# MOS.net
KiCad netlist of a schematic drawn in Altium Designer
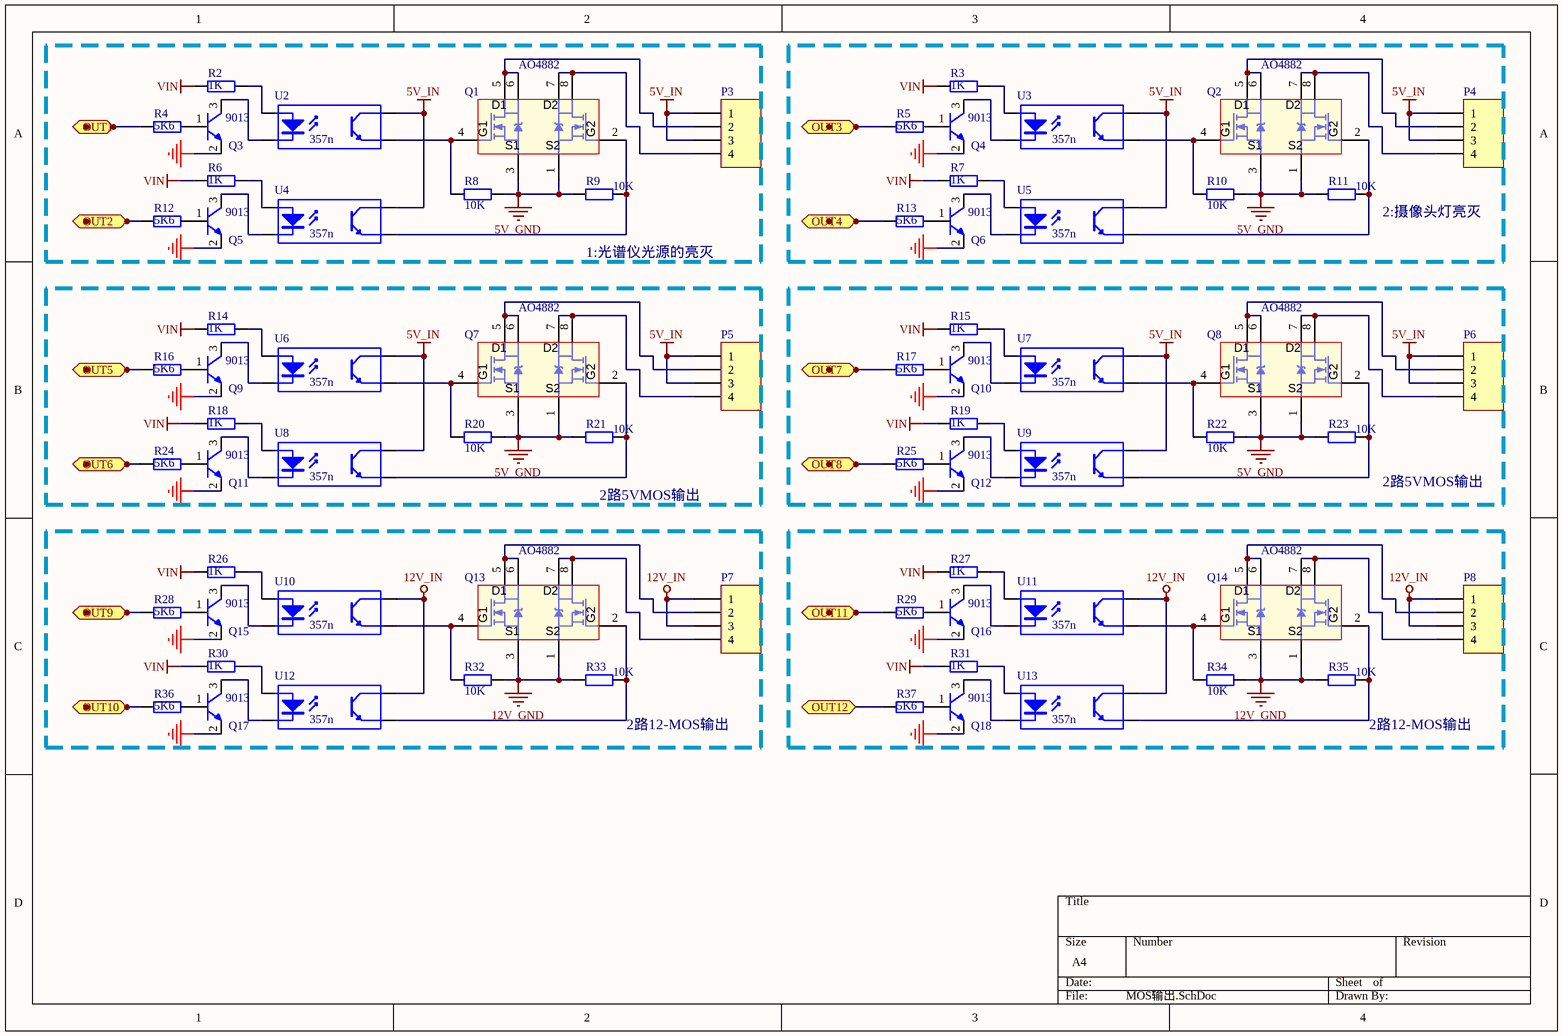
[diagram p0: MOS输出.SchDoc]

(export (version "E")
  (design (tool "Eeschema 10.0.6"))
  (components
    (comp (ref "P3")
      (value "~")
      (footprint "CAN3.81W/4")
      (description "Header, 4-Pin")
      (fields (field (name "PUBLISHER") "Altium Limited"))
      (libsource (lib "Miscellaneous Connectors") (part "Header 4"))
    )
    (comp (ref "P4")
      (value "~")
      (footprint "CAN3.81W/4")
      (description "Header, 4-Pin")
      (fields (field (name "PUBLISHER") "Altium Limited"))
      (libsource (lib "Miscellaneous Connectors") (part "Header 4"))
    )
    (comp (ref "P5")
      (value "~")
      (footprint "CAN3.81W/4")
      (description "Header, 4-Pin")
      (fields (field (name "PUBLISHER") "Altium Limited"))
      (libsource (lib "Miscellaneous Connectors") (part "Header 4"))
    )
    (comp (ref "P6")
      (value "~")
      (footprint "CAN3.81W/4")
      (description "Header, 4-Pin")
      (fields (field (name "PUBLISHER") "Altium Limited"))
      (libsource (lib "Miscellaneous Connectors") (part "Header 4"))
    )
    (comp (ref "P7")
      (value "~")
      (footprint "CAN3.81W/4")
      (description "Header, 4-Pin")
      (fields (field (name "PUBLISHER") "Altium Limited"))
      (libsource (lib "Miscellaneous Connectors") (part "Header 4"))
    )
    (comp (ref "P8")
      (value "~")
      (footprint "CAN3.81W/4")
      (description "Header, 4-Pin")
      (fields (field (name "PUBLISHER") "Altium Limited"))
      (libsource (lib "Miscellaneous Connectors") (part "Header 4"))
    )
    (comp (ref "Q1")
      (value "AO4882")
      (footprint "so8")
      (description "Mosfet Array 2 N-Channel (Dual) 40V 8A 2W Surface Mount 8-SOIC")
      (fields (field (name "MF") "Alpha & Omega Semiconductor Inc."))
      (libsource (lib "TMC5160_RevA") (part "AO4882 MOSFET 2N-CH 40V 8A 8SOIC"))
    )
    (comp (ref "Q2")
      (value "AO4882")
      (footprint "so8")
      (description "Mosfet Array 2 N-Channel (Dual) 40V 8A 2W Surface Mount 8-SOIC")
      (fields (field (name "MF") "Alpha & Omega Semiconductor Inc."))
      (libsource (lib "TMC5160_RevA") (part "AO4882 MOSFET 2N-CH 40V 8A 8SOIC"))
    )
    (comp (ref "Q3") (value "9013") (footprint "sot-23") (libsource (lib "*") (part "NPNBT")))
    (comp (ref "Q4") (value "9013") (footprint "sot-23") (libsource (lib "*") (part "NPNBT")))
    (comp (ref "Q5") (value "9013") (footprint "sot-23") (libsource (lib "*") (part "NPNBT")))
    (comp (ref "Q6") (value "9013") (footprint "sot-23") (libsource (lib "*") (part "NPNBT")))
    (comp (ref "Q7")
      (value "AO4882")
      (footprint "so8")
      (description "Mosfet Array 2 N-Channel (Dual) 40V 8A 2W Surface Mount 8-SOIC")
      (fields (field (name "MF") "Alpha & Omega Semiconductor Inc."))
      (libsource (lib "TMC5160_RevA") (part "AO4882 MOSFET 2N-CH 40V 8A 8SOIC"))
    )
    (comp (ref "Q8")
      (value "AO4882")
      (footprint "so8")
      (description "Mosfet Array 2 N-Channel (Dual) 40V 8A 2W Surface Mount 8-SOIC")
      (fields (field (name "MF") "Alpha & Omega Semiconductor Inc."))
      (libsource (lib "TMC5160_RevA") (part "AO4882 MOSFET 2N-CH 40V 8A 8SOIC"))
    )
    (comp (ref "Q9") (value "9013") (footprint "sot-23") (libsource (lib "*") (part "NPNBT")))
    (comp (ref "Q10") (value "9013") (footprint "sot-23") (libsource (lib "*") (part "NPNBT")))
    (comp (ref "Q11") (value "9013") (footprint "sot-23") (libsource (lib "*") (part "NPNBT")))
    (comp (ref "Q12") (value "9013") (footprint "sot-23") (libsource (lib "*") (part "NPNBT")))
    (comp (ref "Q13")
      (value "AO4882")
      (footprint "so8")
      (description "Mosfet Array 2 N-Channel (Dual) 40V 8A 2W Surface Mount 8-SOIC")
      (fields (field (name "MF") "Alpha & Omega Semiconductor Inc."))
      (libsource (lib "TMC5160_RevA") (part "AO4882 MOSFET 2N-CH 40V 8A 8SOIC"))
    )
    (comp (ref "Q14")
      (value "AO4882")
      (footprint "so8")
      (description "Mosfet Array 2 N-Channel (Dual) 40V 8A 2W Surface Mount 8-SOIC")
      (fields (field (name "MF") "Alpha & Omega Semiconductor Inc."))
      (libsource (lib "TMC5160_RevA") (part "AO4882 MOSFET 2N-CH 40V 8A 8SOIC"))
    )
    (comp (ref "Q15") (value "9013") (footprint "sot-23") (libsource (lib "*") (part "NPNBT")))
    (comp (ref "Q16") (value "9013") (footprint "sot-23") (libsource (lib "*") (part "NPNBT")))
    (comp (ref "Q17") (value "9013") (footprint "sot-23") (libsource (lib "*") (part "NPNBT")))
    (comp (ref "Q18") (value "9013") (footprint "sot-23") (libsource (lib "*") (part "NPNBT")))
    (comp (ref "R2")
      (value "1K")
      (footprint "1608")
      (description "Resistor")
      (fields (field (name "PUBLISHER") "Altium Limited"))
      (libsource (lib "*") (part "Res2"))
    )
    (comp (ref "R3")
      (value "1K")
      (footprint "1608")
      (description "Resistor")
      (fields (field (name "PUBLISHER") "Altium Limited"))
      (libsource (lib "*") (part "Res2"))
    )
    (comp (ref "R4")
      (value "5K6")
      (footprint "1608")
      (description "Resistor")
      (fields (field (name "PUBLISHER") "Altium Limited"))
      (libsource (lib "*") (part "Res2"))
    )
    (comp (ref "R5")
      (value "5K6")
      (footprint "1608")
      (description "Resistor")
      (fields (field (name "PUBLISHER") "Altium Limited"))
      (libsource (lib "*") (part "Res2"))
    )
    (comp (ref "R6")
      (value "1K")
      (footprint "1608")
      (description "Resistor")
      (fields (field (name "PUBLISHER") "Altium Limited"))
      (libsource (lib "*") (part "Res2"))
    )
    (comp (ref "R7")
      (value "1K")
      (footprint "1608")
      (description "Resistor")
      (fields (field (name "PUBLISHER") "Altium Limited"))
      (libsource (lib "*") (part "Res2"))
    )
    (comp (ref "R8")
      (value "10K")
      (footprint "1608")
      (description "Resistor")
      (fields (field (name "PUBLISHER") "Altium Limited"))
      (libsource (lib "*") (part "Res2"))
    )
    (comp (ref "R9")
      (value "10K")
      (footprint "1608")
      (description "Resistor")
      (fields (field (name "PUBLISHER") "Altium Limited"))
      (libsource (lib "*") (part "Res2"))
    )
    (comp (ref "R10")
      (value "10K")
      (footprint "1608")
      (description "Resistor")
      (fields (field (name "PUBLISHER") "Altium Limited"))
      (libsource (lib "*") (part "Res2"))
    )
    (comp (ref "R11")
      (value "10K")
      (footprint "1608")
      (description "Resistor")
      (fields (field (name "PUBLISHER") "Altium Limited"))
      (libsource (lib "*") (part "Res2"))
    )
    (comp (ref "R12")
      (value "5K6")
      (footprint "1608")
      (description "Resistor")
      (fields (field (name "PUBLISHER") "Altium Limited"))
      (libsource (lib "*") (part "Res2"))
    )
    (comp (ref "R13")
      (value "5K6")
      (footprint "1608")
      (description "Resistor")
      (fields (field (name "PUBLISHER") "Altium Limited"))
      (libsource (lib "*") (part "Res2"))
    )
    (comp (ref "R14")
      (value "1K")
      (footprint "1608")
      (description "Resistor")
      (fields (field (name "PUBLISHER") "Altium Limited"))
      (libsource (lib "*") (part "Res2"))
    )
    (comp (ref "R15")
      (value "1K")
      (footprint "1608")
      (description "Resistor")
      (fields (field (name "PUBLISHER") "Altium Limited"))
      (libsource (lib "*") (part "Res2"))
    )
    (comp (ref "R16")
      (value "5K6")
      (footprint "1608")
      (description "Resistor")
      (fields (field (name "PUBLISHER") "Altium Limited"))
      (libsource (lib "*") (part "Res2"))
    )
    (comp (ref "R17")
      (value "5K6")
      (footprint "1608")
      (description "Resistor")
      (fields (field (name "PUBLISHER") "Altium Limited"))
      (libsource (lib "*") (part "Res2"))
    )
    (comp (ref "R18")
      (value "1K")
      (footprint "1608")
      (description "Resistor")
      (fields (field (name "PUBLISHER") "Altium Limited"))
      (libsource (lib "*") (part "Res2"))
    )
    (comp (ref "R19")
      (value "1K")
      (footprint "1608")
      (description "Resistor")
      (fields (field (name "PUBLISHER") "Altium Limited"))
      (libsource (lib "*") (part "Res2"))
    )
    (comp (ref "R20")
      (value "10K")
      (footprint "1608")
      (description "Resistor")
      (fields (field (name "PUBLISHER") "Altium Limited"))
      (libsource (lib "*") (part "Res2"))
    )
    (comp (ref "R21")
      (value "10K")
      (footprint "1608")
      (description "Resistor")
      (fields (field (name "PUBLISHER") "Altium Limited"))
      (libsource (lib "*") (part "Res2"))
    )
    (comp (ref "R22")
      (value "10K")
      (footprint "1608")
      (description "Resistor")
      (fields (field (name "PUBLISHER") "Altium Limited"))
      (libsource (lib "*") (part "Res2"))
    )
    (comp (ref "R23")
      (value "10K")
      (footprint "1608")
      (description "Resistor")
      (fields (field (name "PUBLISHER") "Altium Limited"))
      (libsource (lib "*") (part "Res2"))
    )
    (comp (ref "R24")
      (value "5K6")
      (footprint "1608")
      (description "Resistor")
      (fields (field (name "PUBLISHER") "Altium Limited"))
      (libsource (lib "*") (part "Res2"))
    )
    (comp (ref "R25")
      (value "5K6")
      (footprint "1608")
      (description "Resistor")
      (fields (field (name "PUBLISHER") "Altium Limited"))
      (libsource (lib "*") (part "Res2"))
    )
    (comp (ref "R26")
      (value "1K")
      (footprint "1608")
      (description "Resistor")
      (fields (field (name "PUBLISHER") "Altium Limited"))
      (libsource (lib "*") (part "Res2"))
    )
    (comp (ref "R27")
      (value "1K")
      (footprint "1608")
      (description "Resistor")
      (fields (field (name "PUBLISHER") "Altium Limited"))
      (libsource (lib "*") (part "Res2"))
    )
    (comp (ref "R28")
      (value "5K6")
      (footprint "1608")
      (description "Resistor")
      (fields (field (name "PUBLISHER") "Altium Limited"))
      (libsource (lib "*") (part "Res2"))
    )
    (comp (ref "R29")
      (value "5K6")
      (footprint "1608")
      (description "Resistor")
      (fields (field (name "PUBLISHER") "Altium Limited"))
      (libsource (lib "*") (part "Res2"))
    )
    (comp (ref "R30")
      (value "1K")
      (footprint "1608")
      (description "Resistor")
      (fields (field (name "PUBLISHER") "Altium Limited"))
      (libsource (lib "*") (part "Res2"))
    )
    (comp (ref "R31")
      (value "1K")
      (footprint "1608")
      (description "Resistor")
      (fields (field (name "PUBLISHER") "Altium Limited"))
      (libsource (lib "*") (part "Res2"))
    )
    (comp (ref "R32")
      (value "10K")
      (footprint "1608")
      (description "Resistor")
      (fields (field (name "PUBLISHER") "Altium Limited"))
      (libsource (lib "*") (part "Res2"))
    )
    (comp (ref "R33")
      (value "10K")
      (footprint "1608")
      (description "Resistor")
      (fields (field (name "PUBLISHER") "Altium Limited"))
      (libsource (lib "*") (part "Res2"))
    )
    (comp (ref "R34")
      (value "10K")
      (footprint "1608")
      (description "Resistor")
      (fields (field (name "PUBLISHER") "Altium Limited"))
      (libsource (lib "*") (part "Res2"))
    )
    (comp (ref "R35")
      (value "10K")
      (footprint "1608")
      (description "Resistor")
      (fields (field (name "PUBLISHER") "Altium Limited"))
      (libsource (lib "*") (part "Res2"))
    )
    (comp (ref "R36")
      (value "5K6")
      (footprint "1608")
      (description "Resistor")
      (fields (field (name "PUBLISHER") "Altium Limited"))
      (libsource (lib "*") (part "Res2"))
    )
    (comp (ref "R37")
      (value "5K6")
      (footprint "1608")
      (description "Resistor")
      (fields (field (name "PUBLISHER") "Altium Limited"))
      (libsource (lib "*") (part "Res2"))
    )
    (comp (ref "U2")
      (value "357n")
      (footprint "375N")
      (description "4-Pin Phototransistor Optocoupler")
      (fields (field (name "PUBLISHER") "Altium Limited"))
      (libsource (lib "Miscellaneous Devices") (part "Optoisolator1"))
    )
    (comp (ref "U3")
      (value "357n")
      (footprint "375N")
      (description "4-Pin Phototransistor Optocoupler")
      (fields (field (name "PUBLISHER") "Altium Limited"))
      (libsource (lib "Miscellaneous Devices") (part "Optoisolator1"))
    )
    (comp (ref "U4")
      (value "357n")
      (footprint "375N")
      (description "4-Pin Phototransistor Optocoupler")
      (fields (field (name "PUBLISHER") "Altium Limited"))
      (libsource (lib "Miscellaneous Devices") (part "Optoisolator1"))
    )
    (comp (ref "U5")
      (value "357n")
      (footprint "375N")
      (description "4-Pin Phototransistor Optocoupler")
      (fields (field (name "PUBLISHER") "Altium Limited"))
      (libsource (lib "Miscellaneous Devices") (part "Optoisolator1"))
    )
    (comp (ref "U6")
      (value "357n")
      (footprint "375N")
      (description "4-Pin Phototransistor Optocoupler")
      (fields (field (name "PUBLISHER") "Altium Limited"))
      (libsource (lib "Miscellaneous Devices") (part "Optoisolator1"))
    )
    (comp (ref "U7")
      (value "357n")
      (footprint "375N")
      (description "4-Pin Phototransistor Optocoupler")
      (fields (field (name "PUBLISHER") "Altium Limited"))
      (libsource (lib "Miscellaneous Devices") (part "Optoisolator1"))
    )
    (comp (ref "U8")
      (value "357n")
      (footprint "375N")
      (description "4-Pin Phototransistor Optocoupler")
      (fields (field (name "PUBLISHER") "Altium Limited"))
      (libsource (lib "Miscellaneous Devices") (part "Optoisolator1"))
    )
    (comp (ref "U9")
      (value "357n")
      (footprint "375N")
      (description "4-Pin Phototransistor Optocoupler")
      (fields (field (name "PUBLISHER") "Altium Limited"))
      (libsource (lib "Miscellaneous Devices") (part "Optoisolator1"))
    )
    (comp (ref "U10")
      (value "357n")
      (footprint "375N")
      (description "4-Pin Phototransistor Optocoupler")
      (fields (field (name "PUBLISHER") "Altium Limited"))
      (libsource (lib "Miscellaneous Devices") (part "Optoisolator1"))
    )
    (comp (ref "U11")
      (value "357n")
      (footprint "375N")
      (description "4-Pin Phototransistor Optocoupler")
      (fields (field (name "PUBLISHER") "Altium Limited"))
      (libsource (lib "Miscellaneous Devices") (part "Optoisolator1"))
    )
    (comp (ref "U12")
      (value "357n")
      (footprint "375N")
      (description "4-Pin Phototransistor Optocoupler")
      (fields (field (name "PUBLISHER") "Altium Limited"))
      (libsource (lib "Miscellaneous Devices") (part "Optoisolator1"))
    )
    (comp (ref "U13")
      (value "357n")
      (footprint "375N")
      (description "4-Pin Phototransistor Optocoupler")
      (fields (field (name "PUBLISHER") "Altium Limited"))
      (libsource (lib "Miscellaneous Devices") (part "Optoisolator1"))
    )
  )
  (nets
    (net (code "1") (name "/OUT1") (class "Default")
      (node (ref "R4") (pin "2") (pinfunction "2_2") (pintype "passive"))
    )
    (net (code "2") (name "/OUT2") (class "Default")
      (node (ref "R12") (pin "2") (pinfunction "2_2") (pintype "passive"))
    )
    (net (code "3") (name "/OUT3") (class "Default")
      (node (ref "R5") (pin "2") (pinfunction "2_2") (pintype "passive"))
    )
    (net (code "4") (name "/OUT4") (class "Default")
      (node (ref "R13") (pin "2") (pinfunction "2_2") (pintype "passive"))
    )
    (net (code "5") (name "/OUT5") (class "Default")
      (node (ref "R16") (pin "2") (pinfunction "2_2") (pintype "passive"))
    )
    (net (code "6") (name "/OUT6") (class "Default")
      (node (ref "R24") (pin "2") (pinfunction "2_2") (pintype "passive"))
    )
    (net (code "7") (name "/OUT7") (class "Default")
      (node (ref "R17") (pin "2") (pinfunction "2_2") (pintype "passive"))
    )
    (net (code "8") (name "/OUT8") (class "Default")
      (node (ref "R25") (pin "2") (pinfunction "2_2") (pintype "passive"))
    )
    (net (code "9") (name "/OUT9") (class "Default")
      (node (ref "R28") (pin "2") (pinfunction "2_2") (pintype "passive"))
    )
    (net (code "10") (name "/OUT10") (class "Default")
      (node (ref "R36") (pin "2") (pinfunction "2_2") (pintype "passive"))
    )
    (net (code "11") (name "/OUT11") (class "Default")
      (node (ref "R29") (pin "2") (pinfunction "2_2") (pintype "passive"))
    )
    (net (code "12") (name "/OUT12") (class "Default")
      (node (ref "R37") (pin "2") (pinfunction "2_2") (pintype "passive"))
    )
    (net (code "13") (name "5V_GND") (class "Default")
      (node (ref "Q1") (pin "1") (pinfunction "S2_1") (pintype "passive"))
      (node (ref "Q1") (pin "3") (pinfunction "S1_3") (pintype "passive"))
      (node (ref "Q2") (pin "1") (pinfunction "S2_1") (pintype "passive"))
      (node (ref "Q2") (pin "3") (pinfunction "S1_3") (pintype "passive"))
      (node (ref "Q7") (pin "1") (pinfunction "S2_1") (pintype "passive"))
      (node (ref "Q7") (pin "3") (pinfunction "S1_3") (pintype "passive"))
      (node (ref "Q8") (pin "1") (pinfunction "S2_1") (pintype "passive"))
      (node (ref "Q8") (pin "3") (pinfunction "S1_3") (pintype "passive"))
      (node (ref "R10") (pin "1") (pinfunction "1_1") (pintype "passive"))
      (node (ref "R11") (pin "2") (pinfunction "2_2") (pintype "passive"))
      (node (ref "R20") (pin "1") (pinfunction "1_1") (pintype "passive"))
      (node (ref "R21") (pin "2") (pinfunction "2_2") (pintype "passive"))
      (node (ref "R22") (pin "1") (pinfunction "1_1") (pintype "passive"))
      (node (ref "R23") (pin "2") (pinfunction "2_2") (pintype "passive"))
      (node (ref "R8") (pin "1") (pinfunction "1_1") (pintype "passive"))
      (node (ref "R9") (pin "2") (pinfunction "2_2") (pintype "passive"))
    )
    (net (code "14") (name "5V_IN") (class "Default")
      (node (ref "P3") (pin "1") (pinfunction "1_1") (pintype "passive"))
      (node (ref "P3") (pin "3") (pinfunction "3_3") (pintype "passive"))
      (node (ref "P4") (pin "1") (pinfunction "1_1") (pintype "passive"))
      (node (ref "P4") (pin "3") (pinfunction "3_3") (pintype "passive"))
      (node (ref "P5") (pin "1") (pinfunction "1_1") (pintype "passive"))
      (node (ref "P5") (pin "3") (pinfunction "3_3") (pintype "passive"))
      (node (ref "P6") (pin "1") (pinfunction "1_1") (pintype "passive"))
      (node (ref "P6") (pin "3") (pinfunction "3_3") (pintype "passive"))
      (node (ref "U2") (pin "4") (pinfunction "C_4") (pintype "passive"))
      (node (ref "U3") (pin "4") (pinfunction "C_4") (pintype "passive"))
      (node (ref "U4") (pin "4") (pinfunction "C_4") (pintype "passive"))
      (node (ref "U5") (pin "4") (pinfunction "C_4") (pintype "passive"))
      (node (ref "U6") (pin "4") (pinfunction "C_4") (pintype "passive"))
      (node (ref "U7") (pin "4") (pinfunction "C_4") (pintype "passive"))
      (node (ref "U8") (pin "4") (pinfunction "C_4") (pintype "passive"))
      (node (ref "U9") (pin "4") (pinfunction "C_4") (pintype "passive"))
    )
    (net (code "15") (name "12V_GND") (class "Default")
      (node (ref "Q13") (pin "1") (pinfunction "S2_1") (pintype "passive"))
      (node (ref "Q13") (pin "3") (pinfunction "S1_3") (pintype "passive"))
      (node (ref "Q14") (pin "1") (pinfunction "S2_1") (pintype "passive"))
      (node (ref "Q14") (pin "3") (pinfunction "S1_3") (pintype "passive"))
      (node (ref "R32") (pin "1") (pinfunction "1_1") (pintype "passive"))
      (node (ref "R33") (pin "2") (pinfunction "2_2") (pintype "passive"))
      (node (ref "R34") (pin "1") (pinfunction "1_1") (pintype "passive"))
      (node (ref "R35") (pin "2") (pinfunction "2_2") (pintype "passive"))
    )
    (net (code "16") (name "12V_IN") (class "Default")
      (node (ref "P7") (pin "1") (pinfunction "1_1") (pintype "passive"))
      (node (ref "P7") (pin "3") (pinfunction "3_3") (pintype "passive"))
      (node (ref "P8") (pin "1") (pinfunction "1_1") (pintype "passive"))
      (node (ref "P8") (pin "3") (pinfunction "3_3") (pintype "passive"))
      (node (ref "U10") (pin "4") (pinfunction "C_4") (pintype "passive"))
      (node (ref "U11") (pin "4") (pinfunction "C_4") (pintype "passive"))
      (node (ref "U12") (pin "4") (pinfunction "C_4") (pintype "passive"))
      (node (ref "U13") (pin "4") (pinfunction "C_4") (pintype "passive"))
    )
    (net (code "17") (name "GND") (class "Default")
      (node (ref "Q10") (pin "2") (pinfunction "E_2") (pintype "passive"))
      (node (ref "Q11") (pin "2") (pinfunction "E_2") (pintype "passive"))
      (node (ref "Q12") (pin "2") (pinfunction "E_2") (pintype "passive"))
      (node (ref "Q15") (pin "2") (pinfunction "E_2") (pintype "passive"))
      (node (ref "Q16") (pin "2") (pinfunction "E_2") (pintype "passive"))
      (node (ref "Q17") (pin "2") (pinfunction "E_2") (pintype "passive"))
      (node (ref "Q18") (pin "2") (pinfunction "E_2") (pintype "passive"))
      (node (ref "Q3") (pin "2") (pinfunction "E_2") (pintype "passive"))
      (node (ref "Q4") (pin "2") (pinfunction "E_2") (pintype "passive"))
      (node (ref "Q5") (pin "2") (pinfunction "E_2") (pintype "passive"))
      (node (ref "Q6") (pin "2") (pinfunction "E_2") (pintype "passive"))
      (node (ref "Q9") (pin "2") (pinfunction "E_2") (pintype "passive"))
    )
    (net (code "18") (name "Net-(P3-Pad2)") (class "Default")
      (node (ref "P3") (pin "2") (pinfunction "2_2") (pintype "passive"))
      (node (ref "Q1") (pin "5") (pinfunction "D1_5") (pintype "passive"))
      (node (ref "Q1") (pin "6") (pinfunction "D1_6") (pintype "passive"))
    )
    (net (code "19") (name "Net-(P3-Pad4)") (class "Default")
      (node (ref "P3") (pin "4") (pinfunction "4_4") (pintype "passive"))
      (node (ref "Q1") (pin "7") (pinfunction "D2_7") (pintype "passive"))
      (node (ref "Q1") (pin "8") (pinfunction "D2_8") (pintype "passive"))
    )
    (net (code "20") (name "Net-(P4-Pad2)") (class "Default")
      (node (ref "P4") (pin "2") (pinfunction "2_2") (pintype "passive"))
      (node (ref "Q2") (pin "5") (pinfunction "D1_5") (pintype "passive"))
      (node (ref "Q2") (pin "6") (pinfunction "D1_6") (pintype "passive"))
    )
    (net (code "21") (name "Net-(P4-Pad4)") (class "Default")
      (node (ref "P4") (pin "4") (pinfunction "4_4") (pintype "passive"))
      (node (ref "Q2") (pin "7") (pinfunction "D2_7") (pintype "passive"))
      (node (ref "Q2") (pin "8") (pinfunction "D2_8") (pintype "passive"))
    )
    (net (code "22") (name "Net-(P5-Pad2)") (class "Default")
      (node (ref "P5") (pin "2") (pinfunction "2_2") (pintype "passive"))
      (node (ref "Q7") (pin "5") (pinfunction "D1_5") (pintype "passive"))
      (node (ref "Q7") (pin "6") (pinfunction "D1_6") (pintype "passive"))
    )
    (net (code "23") (name "Net-(P5-Pad4)") (class "Default")
      (node (ref "P5") (pin "4") (pinfunction "4_4") (pintype "passive"))
      (node (ref "Q7") (pin "7") (pinfunction "D2_7") (pintype "passive"))
      (node (ref "Q7") (pin "8") (pinfunction "D2_8") (pintype "passive"))
    )
    (net (code "24") (name "Net-(P6-Pad2)") (class "Default")
      (node (ref "P6") (pin "2") (pinfunction "2_2") (pintype "passive"))
      (node (ref "Q8") (pin "5") (pinfunction "D1_5") (pintype "passive"))
      (node (ref "Q8") (pin "6") (pinfunction "D1_6") (pintype "passive"))
    )
    (net (code "25") (name "Net-(P6-Pad4)") (class "Default")
      (node (ref "P6") (pin "4") (pinfunction "4_4") (pintype "passive"))
      (node (ref "Q8") (pin "7") (pinfunction "D2_7") (pintype "passive"))
      (node (ref "Q8") (pin "8") (pinfunction "D2_8") (pintype "passive"))
    )
    (net (code "26") (name "Net-(P7-Pad2)") (class "Default")
      (node (ref "P7") (pin "2") (pinfunction "2_2") (pintype "passive"))
      (node (ref "Q13") (pin "5") (pinfunction "D1_5") (pintype "passive"))
      (node (ref "Q13") (pin "6") (pinfunction "D1_6") (pintype "passive"))
    )
    (net (code "27") (name "Net-(P7-Pad4)") (class "Default")
      (node (ref "P7") (pin "4") (pinfunction "4_4") (pintype "passive"))
      (node (ref "Q13") (pin "7") (pinfunction "D2_7") (pintype "passive"))
      (node (ref "Q13") (pin "8") (pinfunction "D2_8") (pintype "passive"))
    )
    (net (code "28") (name "Net-(P8-Pad2)") (class "Default")
      (node (ref "P8") (pin "2") (pinfunction "2_2") (pintype "passive"))
      (node (ref "Q14") (pin "5") (pinfunction "D1_5") (pintype "passive"))
      (node (ref "Q14") (pin "6") (pinfunction "D1_6") (pintype "passive"))
    )
    (net (code "29") (name "Net-(P8-Pad4)") (class "Default")
      (node (ref "P8") (pin "4") (pinfunction "4_4") (pintype "passive"))
      (node (ref "Q14") (pin "7") (pinfunction "D2_7") (pintype "passive"))
      (node (ref "Q14") (pin "8") (pinfunction "D2_8") (pintype "passive"))
    )
    (net (code "30") (name "Net-(Q1-G1)") (class "Default")
      (node (ref "Q1") (pin "4") (pinfunction "G1_4") (pintype "passive"))
      (node (ref "R8") (pin "2") (pinfunction "2_2") (pintype "passive"))
      (node (ref "U2") (pin "3") (pinfunction "E_3") (pintype "passive"))
    )
    (net (code "31") (name "Net-(Q1-G2)") (class "Default")
      (node (ref "Q1") (pin "2") (pinfunction "G2_2") (pintype "passive"))
      (node (ref "R9") (pin "1") (pinfunction "1_1") (pintype "passive"))
      (node (ref "U4") (pin "3") (pinfunction "E_3") (pintype "passive"))
    )
    (net (code "32") (name "Net-(Q2-G1)") (class "Default")
      (node (ref "Q2") (pin "4") (pinfunction "G1_4") (pintype "passive"))
      (node (ref "R10") (pin "2") (pinfunction "2_2") (pintype "passive"))
      (node (ref "U3") (pin "3") (pinfunction "E_3") (pintype "passive"))
    )
    (net (code "33") (name "Net-(Q2-G2)") (class "Default")
      (node (ref "Q2") (pin "2") (pinfunction "G2_2") (pintype "passive"))
      (node (ref "R11") (pin "1") (pinfunction "1_1") (pintype "passive"))
      (node (ref "U5") (pin "3") (pinfunction "E_3") (pintype "passive"))
    )
    (net (code "34") (name "Net-(Q3-B)") (class "Default")
      (node (ref "Q3") (pin "1") (pinfunction "B_1") (pintype "passive"))
      (node (ref "R4") (pin "1") (pinfunction "1_1") (pintype "passive"))
    )
    (net (code "35") (name "Net-(Q3-C)") (class "Default")
      (node (ref "Q3") (pin "3") (pinfunction "C_3") (pintype "passive"))
      (node (ref "U2") (pin "2") (pinfunction "K_2") (pintype "passive"))
    )
    (net (code "36") (name "Net-(Q4-B)") (class "Default")
      (node (ref "Q4") (pin "1") (pinfunction "B_1") (pintype "passive"))
      (node (ref "R5") (pin "1") (pinfunction "1_1") (pintype "passive"))
    )
    (net (code "37") (name "Net-(Q4-C)") (class "Default")
      (node (ref "Q4") (pin "3") (pinfunction "C_3") (pintype "passive"))
      (node (ref "U3") (pin "2") (pinfunction "K_2") (pintype "passive"))
    )
    (net (code "38") (name "Net-(Q5-B)") (class "Default")
      (node (ref "Q5") (pin "1") (pinfunction "B_1") (pintype "passive"))
      (node (ref "R12") (pin "1") (pinfunction "1_1") (pintype "passive"))
    )
    (net (code "39") (name "Net-(Q5-C)") (class "Default")
      (node (ref "Q5") (pin "3") (pinfunction "C_3") (pintype "passive"))
      (node (ref "U4") (pin "2") (pinfunction "K_2") (pintype "passive"))
    )
    (net (code "40") (name "Net-(Q6-B)") (class "Default")
      (node (ref "Q6") (pin "1") (pinfunction "B_1") (pintype "passive"))
      (node (ref "R13") (pin "1") (pinfunction "1_1") (pintype "passive"))
    )
    (net (code "41") (name "Net-(Q6-C)") (class "Default")
      (node (ref "Q6") (pin "3") (pinfunction "C_3") (pintype "passive"))
      (node (ref "U5") (pin "2") (pinfunction "K_2") (pintype "passive"))
    )
    (net (code "42") (name "Net-(Q7-G1)") (class "Default")
      (node (ref "Q7") (pin "4") (pinfunction "G1_4") (pintype "passive"))
      (node (ref "R20") (pin "2") (pinfunction "2_2") (pintype "passive"))
      (node (ref "U6") (pin "3") (pinfunction "E_3") (pintype "passive"))
    )
    (net (code "43") (name "Net-(Q7-G2)") (class "Default")
      (node (ref "Q7") (pin "2") (pinfunction "G2_2") (pintype "passive"))
      (node (ref "R21") (pin "1") (pinfunction "1_1") (pintype "passive"))
      (node (ref "U8") (pin "3") (pinfunction "E_3") (pintype "passive"))
    )
    (net (code "44") (name "Net-(Q8-G1)") (class "Default")
      (node (ref "Q8") (pin "4") (pinfunction "G1_4") (pintype "passive"))
      (node (ref "R22") (pin "2") (pinfunction "2_2") (pintype "passive"))
      (node (ref "U7") (pin "3") (pinfunction "E_3") (pintype "passive"))
    )
    (net (code "45") (name "Net-(Q8-G2)") (class "Default")
      (node (ref "Q8") (pin "2") (pinfunction "G2_2") (pintype "passive"))
      (node (ref "R23") (pin "1") (pinfunction "1_1") (pintype "passive"))
      (node (ref "U9") (pin "3") (pinfunction "E_3") (pintype "passive"))
    )
    (net (code "46") (name "Net-(Q9-B)") (class "Default")
      (node (ref "Q9") (pin "1") (pinfunction "B_1") (pintype "passive"))
      (node (ref "R16") (pin "1") (pinfunction "1_1") (pintype "passive"))
    )
    (net (code "47") (name "Net-(Q9-C)") (class "Default")
      (node (ref "Q9") (pin "3") (pinfunction "C_3") (pintype "passive"))
      (node (ref "U6") (pin "2") (pinfunction "K_2") (pintype "passive"))
    )
    (net (code "48") (name "Net-(Q10-B)") (class "Default")
      (node (ref "Q10") (pin "1") (pinfunction "B_1") (pintype "passive"))
      (node (ref "R17") (pin "1") (pinfunction "1_1") (pintype "passive"))
    )
    (net (code "49") (name "Net-(Q10-C)") (class "Default")
      (node (ref "Q10") (pin "3") (pinfunction "C_3") (pintype "passive"))
      (node (ref "U7") (pin "2") (pinfunction "K_2") (pintype "passive"))
    )
    (net (code "50") (name "Net-(Q11-B)") (class "Default")
      (node (ref "Q11") (pin "1") (pinfunction "B_1") (pintype "passive"))
      (node (ref "R24") (pin "1") (pinfunction "1_1") (pintype "passive"))
    )
    (net (code "51") (name "Net-(Q11-C)") (class "Default")
      (node (ref "Q11") (pin "3") (pinfunction "C_3") (pintype "passive"))
      (node (ref "U8") (pin "2") (pinfunction "K_2") (pintype "passive"))
    )
    (net (code "52") (name "Net-(Q12-B)") (class "Default")
      (node (ref "Q12") (pin "1") (pinfunction "B_1") (pintype "passive"))
      (node (ref "R25") (pin "1") (pinfunction "1_1") (pintype "passive"))
    )
    (net (code "53") (name "Net-(Q12-C)") (class "Default")
      (node (ref "Q12") (pin "3") (pinfunction "C_3") (pintype "passive"))
      (node (ref "U9") (pin "2") (pinfunction "K_2") (pintype "passive"))
    )
    (net (code "54") (name "Net-(Q13-G1)") (class "Default")
      (node (ref "Q13") (pin "4") (pinfunction "G1_4") (pintype "passive"))
      (node (ref "R32") (pin "2") (pinfunction "2_2") (pintype "passive"))
      (node (ref "U10") (pin "3") (pinfunction "E_3") (pintype "passive"))
    )
    (net (code "55") (name "Net-(Q13-G2)") (class "Default")
      (node (ref "Q13") (pin "2") (pinfunction "G2_2") (pintype "passive"))
      (node (ref "R33") (pin "1") (pinfunction "1_1") (pintype "passive"))
      (node (ref "U12") (pin "3") (pinfunction "E_3") (pintype "passive"))
    )
    (net (code "56") (name "Net-(Q14-G1)") (class "Default")
      (node (ref "Q14") (pin "4") (pinfunction "G1_4") (pintype "passive"))
      (node (ref "R34") (pin "2") (pinfunction "2_2") (pintype "passive"))
      (node (ref "U11") (pin "3") (pinfunction "E_3") (pintype "passive"))
    )
    (net (code "57") (name "Net-(Q14-G2)") (class "Default")
      (node (ref "Q14") (pin "2") (pinfunction "G2_2") (pintype "passive"))
      (node (ref "R35") (pin "1") (pinfunction "1_1") (pintype "passive"))
      (node (ref "U13") (pin "3") (pinfunction "E_3") (pintype "passive"))
    )
    (net (code "58") (name "Net-(Q15-B)") (class "Default")
      (node (ref "Q15") (pin "1") (pinfunction "B_1") (pintype "passive"))
      (node (ref "R28") (pin "1") (pinfunction "1_1") (pintype "passive"))
    )
    (net (code "59") (name "Net-(Q15-C)") (class "Default")
      (node (ref "Q15") (pin "3") (pinfunction "C_3") (pintype "passive"))
      (node (ref "U10") (pin "2") (pinfunction "K_2") (pintype "passive"))
    )
    (net (code "60") (name "Net-(Q16-B)") (class "Default")
      (node (ref "Q16") (pin "1") (pinfunction "B_1") (pintype "passive"))
      (node (ref "R29") (pin "1") (pinfunction "1_1") (pintype "passive"))
    )
    (net (code "61") (name "Net-(Q16-C)") (class "Default")
      (node (ref "Q16") (pin "3") (pinfunction "C_3") (pintype "passive"))
      (node (ref "U11") (pin "2") (pinfunction "K_2") (pintype "passive"))
    )
    (net (code "62") (name "Net-(Q17-B)") (class "Default")
      (node (ref "Q17") (pin "1") (pinfunction "B_1") (pintype "passive"))
      (node (ref "R36") (pin "1") (pinfunction "1_1") (pintype "passive"))
    )
    (net (code "63") (name "Net-(Q17-C)") (class "Default")
      (node (ref "Q17") (pin "3") (pinfunction "C_3") (pintype "passive"))
      (node (ref "U12") (pin "2") (pinfunction "K_2") (pintype "passive"))
    )
    (net (code "64") (name "Net-(Q18-B)") (class "Default")
      (node (ref "Q18") (pin "1") (pinfunction "B_1") (pintype "passive"))
      (node (ref "R37") (pin "1") (pinfunction "1_1") (pintype "passive"))
    )
    (net (code "65") (name "Net-(Q18-C)") (class "Default")
      (node (ref "Q18") (pin "3") (pinfunction "C_3") (pintype "passive"))
      (node (ref "U13") (pin "2") (pinfunction "K_2") (pintype "passive"))
    )
    (net (code "66") (name "Net-(U2-A)") (class "Default")
      (node (ref "R2") (pin "1") (pinfunction "1_1") (pintype "passive"))
      (node (ref "U2") (pin "1") (pinfunction "A_1") (pintype "passive"))
    )
    (net (code "67") (name "Net-(U3-A)") (class "Default")
      (node (ref "R3") (pin "1") (pinfunction "1_1") (pintype "passive"))
      (node (ref "U3") (pin "1") (pinfunction "A_1") (pintype "passive"))
    )
    (net (code "68") (name "Net-(U4-A)") (class "Default")
      (node (ref "R6") (pin "1") (pinfunction "1_1") (pintype "passive"))
      (node (ref "U4") (pin "1") (pinfunction "A_1") (pintype "passive"))
    )
    (net (code "69") (name "Net-(U5-A)") (class "Default")
      (node (ref "R7") (pin "1") (pinfunction "1_1") (pintype "passive"))
      (node (ref "U5") (pin "1") (pinfunction "A_1") (pintype "passive"))
    )
    (net (code "70") (name "Net-(U6-A)") (class "Default")
      (node (ref "R14") (pin "1") (pinfunction "1_1") (pintype "passive"))
      (node (ref "U6") (pin "1") (pinfunction "A_1") (pintype "passive"))
    )
    (net (code "71") (name "Net-(U7-A)") (class "Default")
      (node (ref "R15") (pin "1") (pinfunction "1_1") (pintype "passive"))
      (node (ref "U7") (pin "1") (pinfunction "A_1") (pintype "passive"))
    )
    (net (code "72") (name "Net-(U8-A)") (class "Default")
      (node (ref "R18") (pin "1") (pinfunction "1_1") (pintype "passive"))
      (node (ref "U8") (pin "1") (pinfunction "A_1") (pintype "passive"))
    )
    (net (code "73") (name "Net-(U9-A)") (class "Default")
      (node (ref "R19") (pin "1") (pinfunction "1_1") (pintype "passive"))
      (node (ref "U9") (pin "1") (pinfunction "A_1") (pintype "passive"))
    )
    (net (code "74") (name "Net-(U10-A)") (class "Default")
      (node (ref "R26") (pin "1") (pinfunction "1_1") (pintype "passive"))
      (node (ref "U10") (pin "1") (pinfunction "A_1") (pintype "passive"))
    )
    (net (code "75") (name "Net-(U11-A)") (class "Default")
      (node (ref "R27") (pin "1") (pinfunction "1_1") (pintype "passive"))
      (node (ref "U11") (pin "1") (pinfunction "A_1") (pintype "passive"))
    )
    (net (code "76") (name "Net-(U12-A)") (class "Default")
      (node (ref "R30") (pin "1") (pinfunction "1_1") (pintype "passive"))
      (node (ref "U12") (pin "1") (pinfunction "A_1") (pintype "passive"))
    )
    (net (code "77") (name "Net-(U13-A)") (class "Default")
      (node (ref "R31") (pin "1") (pinfunction "1_1") (pintype "passive"))
      (node (ref "U13") (pin "1") (pinfunction "A_1") (pintype "passive"))
    )
    (net (code "78") (name "VIN") (class "Default")
      (node (ref "R14") (pin "2") (pinfunction "2_2") (pintype "passive"))
      (node (ref "R15") (pin "2") (pinfunction "2_2") (pintype "passive"))
      (node (ref "R18") (pin "2") (pinfunction "2_2") (pintype "passive"))
      (node (ref "R19") (pin "2") (pinfunction "2_2") (pintype "passive"))
      (node (ref "R2") (pin "2") (pinfunction "2_2") (pintype "passive"))
      (node (ref "R26") (pin "2") (pinfunction "2_2") (pintype "passive"))
      (node (ref "R27") (pin "2") (pinfunction "2_2") (pintype "passive"))
      (node (ref "R3") (pin "2") (pinfunction "2_2") (pintype "passive"))
      (node (ref "R30") (pin "2") (pinfunction "2_2") (pintype "passive"))
      (node (ref "R31") (pin "2") (pinfunction "2_2") (pintype "passive"))
      (node (ref "R6") (pin "2") (pinfunction "2_2") (pintype "passive"))
      (node (ref "R7") (pin "2") (pinfunction "2_2") (pintype "passive"))
    )
  )
)
